# sc88_sampler.net
KiCad netlist of a schematic drawn in EAGLE
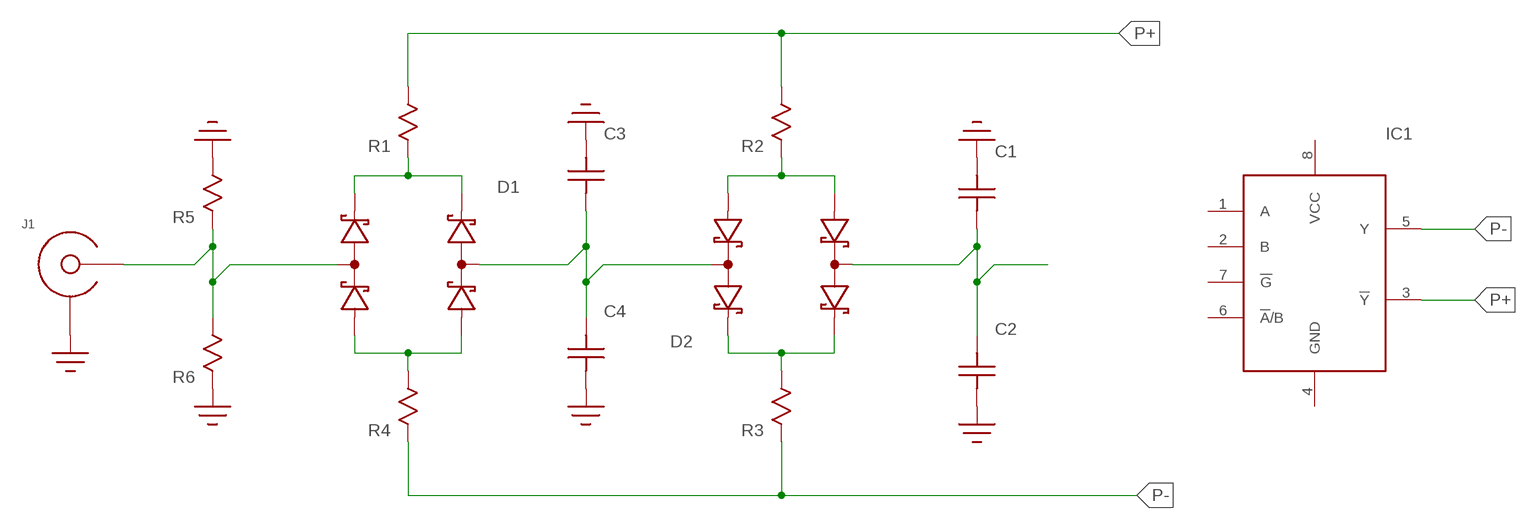
[diagram p0: schematic, sheet 1]

(export (version "E")
  (design (tool "Eeschema 10.0.6"))
  (components
    (comp (ref "C1") (value "C") (footprint "eagle-import:C0402") (libsource (lib "eagle-import") (part "C")))
    (comp (ref "C2") (value "C") (footprint "eagle-import:C0402") (libsource (lib "eagle-import") (part "C")))
    (comp (ref "C3") (value "C") (footprint "eagle-import:C0402") (libsource (lib "eagle-import") (part "C")))
    (comp (ref "C4") (value "C") (footprint "eagle-import:C0402") (libsource (lib "eagle-import") (part "C")))
    (comp (ref "D1")
      (value "SMS3923-081")
      (footprint "eagle-import:SC-88")
      (libsource (lib "eagle-import") (part "SMS3923-081"))
    )
    (comp (ref "D2")
      (value "SMS3923-081")
      (footprint "eagle-import:SC-88")
      (libsource (lib "eagle-import") (part "SMS3923-081"))
    )
    (comp (ref "IC1")
      (value "74LVC2G157")
      (footprint "eagle-import:SSOP8")
      (libsource (lib "eagle-import") (part "74LVC2G157"))
    )
    (comp (ref "J1")
      (value "EDGE_LAUNCH_JACK")
      (footprint "eagle-import:EDGE_LAUNCH_RF_CON")
      (libsource (lib "eagle-import") (part "EDGE_LAUNCH_JACK"))
    )
    (comp (ref "R1")
      (value "R0402")
      (footprint "eagle-import:0402")
      (libsource (lib "eagle-import") (part "R0402"))
    )
    (comp (ref "R2")
      (value "R0402")
      (footprint "eagle-import:0402")
      (libsource (lib "eagle-import") (part "R0402"))
    )
    (comp (ref "R3")
      (value "R0402")
      (footprint "eagle-import:0402")
      (libsource (lib "eagle-import") (part "R0402"))
    )
    (comp (ref "R4")
      (value "R0402")
      (footprint "eagle-import:0402")
      (libsource (lib "eagle-import") (part "R0402"))
    )
    (comp (ref "R5")
      (value "R0402")
      (footprint "eagle-import:0402")
      (libsource (lib "eagle-import") (part "R0402"))
    )
    (comp (ref "R6")
      (value "R0402")
      (footprint "eagle-import:0402")
      (libsource (lib "eagle-import") (part "R0402"))
    )
  )
  (nets
    (net (code "1") (name "GND") (class "Default")
      (node (ref "C1") (pin "2") (pinfunction "P$2_2") (pintype "bidirectional"))
      (node (ref "C2") (pin "1") (pinfunction "P$1_1") (pintype "bidirectional"))
      (node (ref "C3") (pin "2") (pinfunction "P$2_2") (pintype "bidirectional"))
      (node (ref "C4") (pin "1") (pinfunction "P$1_1") (pintype "bidirectional"))
      (node (ref "J1") (pin "GND@1") (pinfunction "SHIELD_GND@1") (pintype "bidirectional"))
      (node (ref "J1") (pin "GND@10") (pinfunction "SHIELD_GND@10") (pintype "bidirectional"))
      (node (ref "J1") (pin "GND@11") (pinfunction "SHIELD_GND@11") (pintype "bidirectional"))
      (node (ref "J1") (pin "GND@12") (pinfunction "SHIELD_GND@12") (pintype "bidirectional"))
      (node (ref "J1") (pin "GND@2") (pinfunction "SHIELD_GND@2") (pintype "bidirectional"))
      (node (ref "J1") (pin "GND@3") (pinfunction "SHIELD_GND@3") (pintype "bidirectional"))
      (node (ref "J1") (pin "GND@4") (pinfunction "SHIELD_GND@4") (pintype "bidirectional"))
      (node (ref "J1") (pin "GND@5") (pinfunction "SHIELD_GND@5") (pintype "bidirectional"))
      (node (ref "J1") (pin "GND@6") (pinfunction "SHIELD_GND@6") (pintype "bidirectional"))
      (node (ref "J1") (pin "GND@7") (pinfunction "SHIELD_GND@7") (pintype "bidirectional"))
      (node (ref "J1") (pin "GND@8") (pinfunction "SHIELD_GND@8") (pintype "bidirectional"))
      (node (ref "J1") (pin "GND@9") (pinfunction "SHIELD_GND@9") (pintype "bidirectional"))
      (node (ref "J1") (pin "SHIELD@1") (pinfunction "SHIELD_SHIELD@1") (pintype "bidirectional"))
      (node (ref "J1") (pin "SHIELD@2") (pinfunction "SHIELD_SHIELD@2") (pintype "bidirectional"))
      (node (ref "R5") (pin "2") (pinfunction "P$4_2") (pintype "bidirectional"))
      (node (ref "R6") (pin "1") (pinfunction "P$3_1") (pintype "bidirectional"))
    )
    (net (code "2") (name "Net-(C1-P$1)") (class "Default")
      (node (ref "C1") (pin "1") (pinfunction "P$1_1") (pintype "bidirectional"))
      (node (ref "C2") (pin "2") (pinfunction "P$2_2") (pintype "bidirectional"))
      (node (ref "D2") (pin "5") (pinfunction "COMMON1_5") (pintype "bidirectional"))
    )
    (net (code "3") (name "Net-(C3-P$1)") (class "Default")
      (node (ref "C3") (pin "1") (pinfunction "P$1_1") (pintype "bidirectional"))
      (node (ref "C4") (pin "2") (pinfunction "P$2_2") (pintype "bidirectional"))
      (node (ref "D1") (pin "2") (pinfunction "COMMON0_2") (pintype "bidirectional"))
      (node (ref "D2") (pin "2") (pinfunction "COMMON0_2") (pintype "bidirectional"))
    )
    (net (code "4") (name "Net-(D1-ANODE0)") (class "Default")
      (node (ref "D1") (pin "1") (pinfunction "ANODE0_1") (pintype "bidirectional"))
      (node (ref "D1") (pin "6") (pinfunction "ANODE1_6") (pintype "bidirectional"))
      (node (ref "R4") (pin "2") (pinfunction "P$4_2") (pintype "bidirectional"))
    )
    (net (code "5") (name "Net-(D1-CATHODE0)") (class "Default")
      (node (ref "D1") (pin "3") (pinfunction "CATHODE0_3") (pintype "bidirectional"))
      (node (ref "D1") (pin "4") (pinfunction "CATHODE1_4") (pintype "bidirectional"))
      (node (ref "R1") (pin "1") (pinfunction "P$3_1") (pintype "bidirectional"))
    )
    (net (code "6") (name "Net-(D1-COMMON1)") (class "Default")
      (node (ref "D1") (pin "5") (pinfunction "COMMON1_5") (pintype "bidirectional"))
      (node (ref "J1") (pin "CENTER") (pinfunction "CENTER_CENTER") (pintype "bidirectional"))
      (node (ref "R5") (pin "1") (pinfunction "P$3_1") (pintype "bidirectional"))
      (node (ref "R6") (pin "2") (pinfunction "P$4_2") (pintype "bidirectional"))
    )
    (net (code "7") (name "Net-(D2-ANODE0)") (class "Default")
      (node (ref "D2") (pin "1") (pinfunction "ANODE0_1") (pintype "bidirectional"))
      (node (ref "D2") (pin "6") (pinfunction "ANODE1_6") (pintype "bidirectional"))
      (node (ref "R2") (pin "1") (pinfunction "P$3_1") (pintype "bidirectional"))
    )
    (net (code "8") (name "Net-(D2-CATHODE0)") (class "Default")
      (node (ref "D2") (pin "3") (pinfunction "CATHODE0_3") (pintype "bidirectional"))
      (node (ref "D2") (pin "4") (pinfunction "CATHODE1_4") (pintype "bidirectional"))
      (node (ref "R3") (pin "2") (pinfunction "P$4_2") (pintype "bidirectional"))
    )
    (net (code "9") (name "P+") (class "Default")
      (node (ref "IC1") (pin "3") (pinfunction "~{Y}_3") (pintype "bidirectional"))
      (node (ref "R1") (pin "2") (pinfunction "P$4_2") (pintype "bidirectional"))
      (node (ref "R2") (pin "2") (pinfunction "P$4_2") (pintype "bidirectional"))
    )
    (net (code "10") (name "P-") (class "Default")
      (node (ref "IC1") (pin "5") (pinfunction "Y_5") (pintype "bidirectional"))
      (node (ref "R3") (pin "1") (pinfunction "P$3_1") (pintype "bidirectional"))
      (node (ref "R4") (pin "1") (pinfunction "P$3_1") (pintype "bidirectional"))
    )
    (net (code "11") (name "unconnected-(IC1-A-Pad1)") (class "Default")
      (node (ref "IC1") (pin "1") (pinfunction "A_1") (pintype "bidirectional"))
    )
    (net (code "12") (name "unconnected-(IC1-B-Pad2)") (class "Default")
      (node (ref "IC1") (pin "2") (pinfunction "B_2") (pintype "bidirectional"))
    )
    (net (code "13") (name "unconnected-(IC1-GND-Pad4)") (class "Default")
      (node (ref "IC1") (pin "4") (pinfunction "GND_4") (pintype "bidirectional"))
    )
    (net (code "14") (name "unconnected-(IC1-VCC-Pad8)") (class "Default")
      (node (ref "IC1") (pin "8") (pinfunction "VCC_8") (pintype "bidirectional"))
    )
    (net (code "15") (name "unconnected-(IC1-~{A}{slash}B-Pad6)") (class "Default")
      (node (ref "IC1") (pin "6") (pinfunction "~{A}/B_6") (pintype "bidirectional"))
    )
    (net (code "16") (name "unconnected-(IC1-~{G}-Pad7)") (class "Default")
      (node (ref "IC1") (pin "7") (pinfunction "~{G}_7") (pintype "bidirectional"))
    )
  )
)
